# BaliseEmetteur.net
KiCad netlist of a schematic drawn in EAGLE
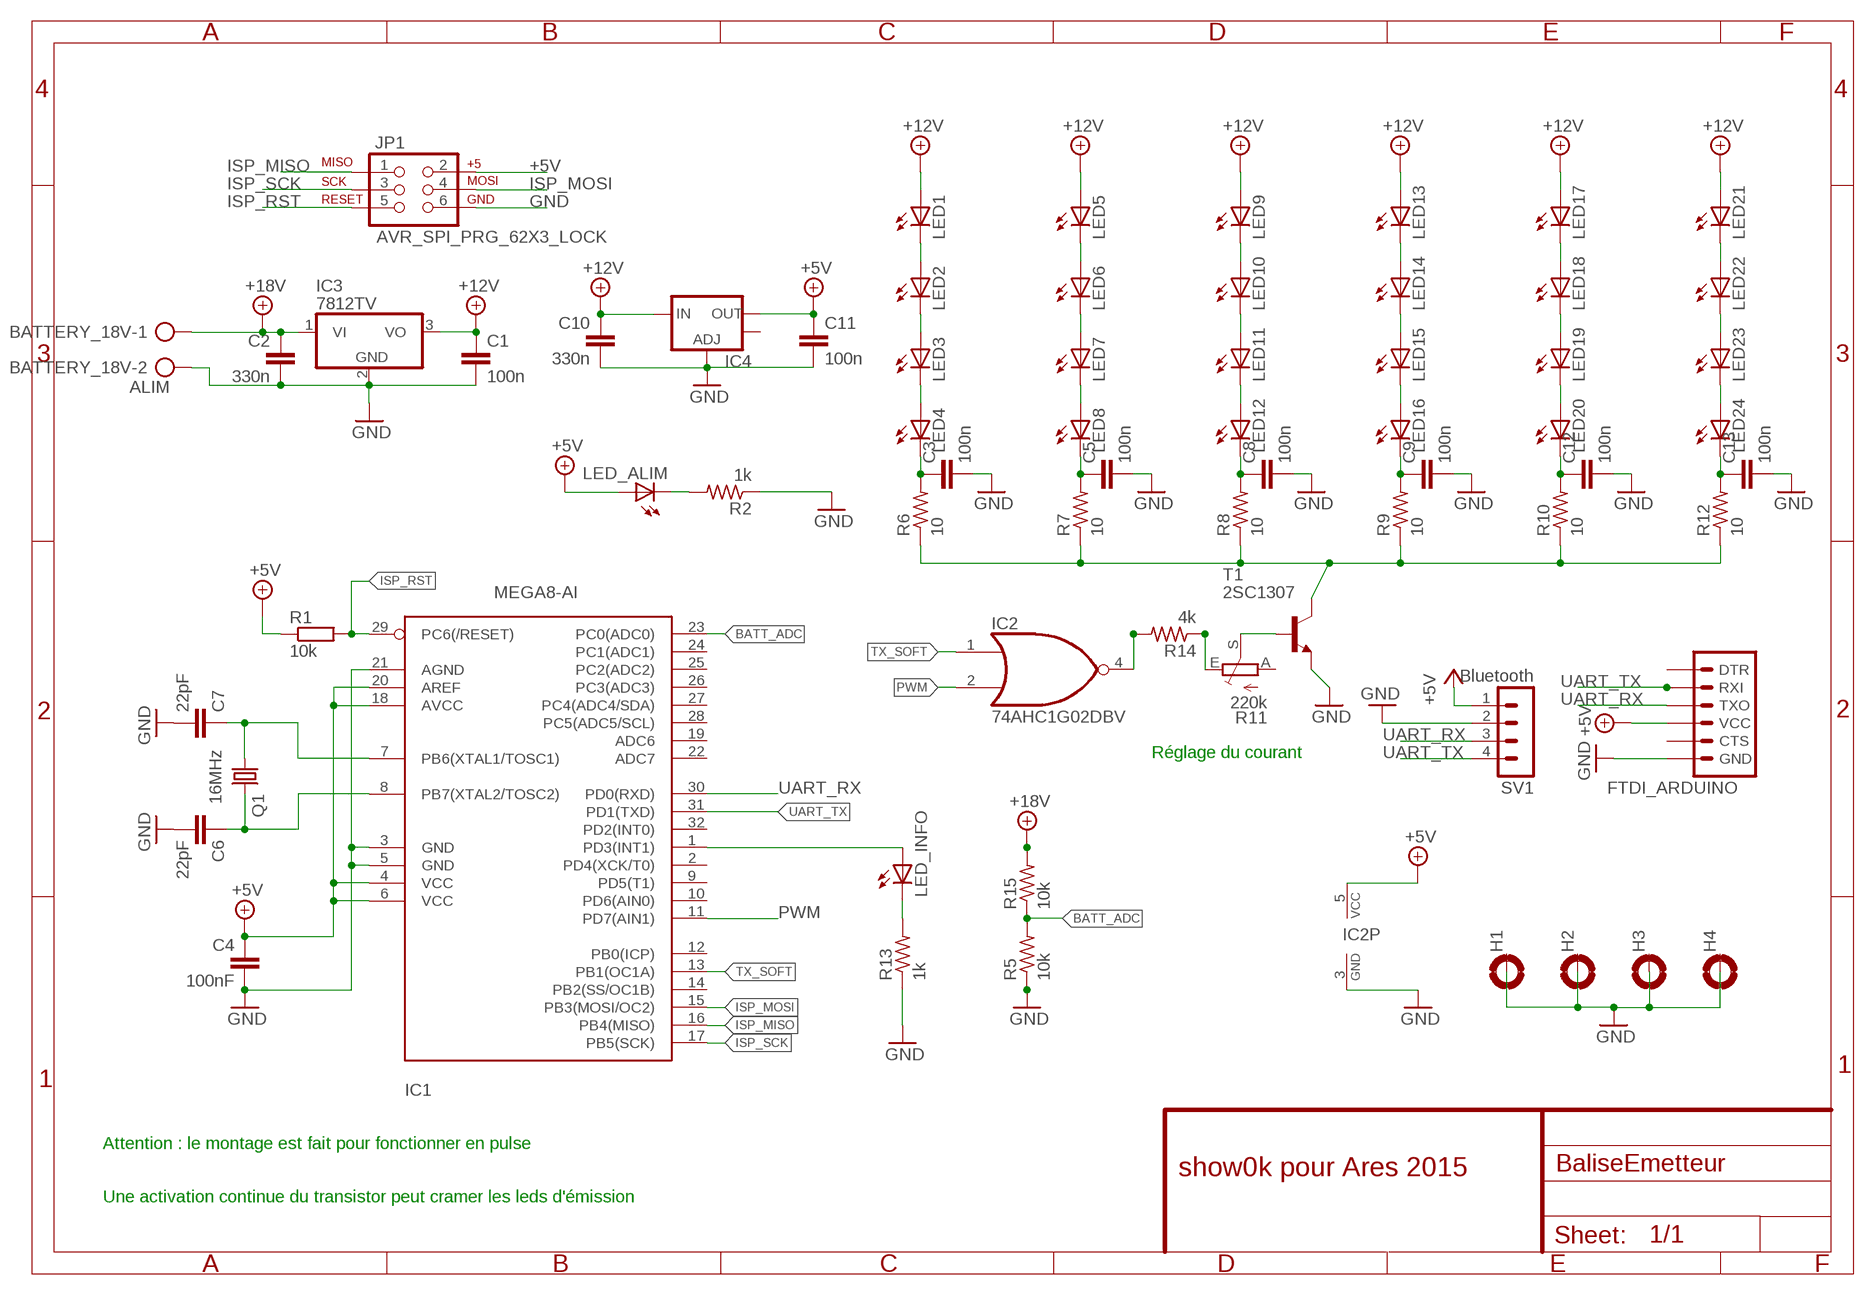
[diagram p0: schematic, sheet 1]

(export (version "E")
  (design (tool "Eeschema 10.0.6"))
  (components
    (comp (ref "BATTERY_18V")
      (value "ALIM")
      (footprint "eagle-import:AK500_2")
      (libsource (lib "eagle-import") (part "AK500/2"))
    )
    (comp (ref "C1")
      (value "100n")
      (footprint "eagle-import:C0805")
      (libsource (lib "eagle-import") (part "C-EUC0805"))
    )
    (comp (ref "C2")
      (value "330n")
      (footprint "eagle-import:C0805")
      (libsource (lib "eagle-import") (part "C-EUC0805"))
    )
    (comp (ref "C3")
      (value "100n")
      (footprint "eagle-import:C0805")
      (libsource (lib "eagle-import") (part "C-EUC0805"))
    )
    (comp (ref "C4")
      (value "100nF")
      (footprint "eagle-import:C0805")
      (libsource (lib "eagle-import") (part "C-EUC0805"))
    )
    (comp (ref "C5")
      (value "100n")
      (footprint "eagle-import:C0805")
      (libsource (lib "eagle-import") (part "C-EUC0805"))
    )
    (comp (ref "C6")
      (value "22pF")
      (footprint "eagle-import:C0805")
      (libsource (lib "eagle-import") (part "C-EUC0805"))
    )
    (comp (ref "C7")
      (value "22pF")
      (footprint "eagle-import:C0805")
      (libsource (lib "eagle-import") (part "C-EUC0805"))
    )
    (comp (ref "C8")
      (value "100n")
      (footprint "eagle-import:C0805")
      (libsource (lib "eagle-import") (part "C-EUC0805"))
    )
    (comp (ref "C9")
      (value "100n")
      (footprint "eagle-import:C0805")
      (libsource (lib "eagle-import") (part "C-EUC0805"))
    )
    (comp (ref "C10")
      (value "330n")
      (footprint "eagle-import:C0805")
      (libsource (lib "eagle-import") (part "C-EUC0805"))
    )
    (comp (ref "C11")
      (value "100n")
      (footprint "eagle-import:C0805")
      (libsource (lib "eagle-import") (part "C-EUC0805"))
    )
    (comp (ref "C12")
      (value "100n")
      (footprint "eagle-import:C0805")
      (libsource (lib "eagle-import") (part "C-EUC0805"))
    )
    (comp (ref "C13")
      (value "100n")
      (footprint "eagle-import:C0805")
      (libsource (lib "eagle-import") (part "C-EUC0805"))
    )
    (comp (ref "FTDI_ARDUINO")
      (value "ARDUINO_SERIAL_PROGRAMPTH")
      (footprint "eagle-import:1X06")
      (libsource (lib "eagle-import") (part "ARDUINO_SERIAL_PROGRAMPTH"))
    )
    (comp (ref "H1")
      (value "MOUNT-PAD-ROUND3.2")
      (footprint "eagle-import:3,2-PAD")
      (libsource (lib "eagle-import") (part "MOUNT-PAD-ROUND3.2"))
    )
    (comp (ref "H2")
      (value "MOUNT-PAD-ROUND3.2")
      (footprint "eagle-import:3,2-PAD")
      (libsource (lib "eagle-import") (part "MOUNT-PAD-ROUND3.2"))
    )
    (comp (ref "H3")
      (value "MOUNT-PAD-ROUND3.2")
      (footprint "eagle-import:3,2-PAD")
      (libsource (lib "eagle-import") (part "MOUNT-PAD-ROUND3.2"))
    )
    (comp (ref "H4")
      (value "MOUNT-PAD-ROUND3.2")
      (footprint "eagle-import:3,2-PAD")
      (libsource (lib "eagle-import") (part "MOUNT-PAD-ROUND3.2"))
    )
    (comp (ref "IC1")
      (value "MEGA8-AI")
      (footprint "eagle-import:TQFP32-08")
      (libsource (lib "eagle-import") (part "MEGA8-AI"))
    )
    (comp (ref "IC2")
      (value "74AHC1G02DBV")
      (footprint "eagle-import:SOT23-5")
      (libsource (lib "eagle-import") (part "741G02DBVAHC"))
    )
    (comp (ref "IC3")
      (value "7812TV")
      (footprint "eagle-import:TO220V")
      (libsource (lib "eagle-import") (part "78TV12"))
    )
    (comp (ref "IC4")
      (value "V_REG_LM1117SOT223")
      (footprint "eagle-import:SOT223")
      (libsource (lib "eagle-import") (part "V_REG_LM1117SOT223"))
    )
    (comp (ref "JP1")
      (value "AVR_SPI_PRG_62X3_LOCK")
      (footprint "eagle-import:2X3_LOCK")
      (libsource (lib "eagle-import") (part "AVR_SPI_PRG_62X3_LOCK"))
    )
    (comp (ref "LED1")
      (value "LEDB155")
      (footprint "eagle-import:Q62902-B155")
      (libsource (lib "eagle-import") (part "led_LEDB155"))
    )
    (comp (ref "LED2")
      (value "LEDB155")
      (footprint "eagle-import:Q62902-B155")
      (libsource (lib "eagle-import") (part "led_LEDB155"))
    )
    (comp (ref "LED3")
      (value "LEDB155")
      (footprint "eagle-import:Q62902-B155")
      (libsource (lib "eagle-import") (part "led_LEDB155"))
    )
    (comp (ref "LED4")
      (value "LEDB155")
      (footprint "eagle-import:Q62902-B155")
      (libsource (lib "eagle-import") (part "led_LEDB155"))
    )
    (comp (ref "LED5")
      (value "LEDB155")
      (footprint "eagle-import:Q62902-B155")
      (libsource (lib "eagle-import") (part "led_LEDB155"))
    )
    (comp (ref "LED6")
      (value "LEDB155")
      (footprint "eagle-import:Q62902-B155")
      (libsource (lib "eagle-import") (part "led_LEDB155"))
    )
    (comp (ref "LED7")
      (value "LEDB155")
      (footprint "eagle-import:Q62902-B155")
      (libsource (lib "eagle-import") (part "led_LEDB155"))
    )
    (comp (ref "LED8")
      (value "LEDB155")
      (footprint "eagle-import:Q62902-B155")
      (libsource (lib "eagle-import") (part "led_LEDB155"))
    )
    (comp (ref "LED9")
      (value "LEDB155")
      (footprint "eagle-import:Q62902-B155")
      (libsource (lib "eagle-import") (part "led_LEDB155"))
    )
    (comp (ref "LED10")
      (value "LEDB155")
      (footprint "eagle-import:Q62902-B155")
      (libsource (lib "eagle-import") (part "led_LEDB155"))
    )
    (comp (ref "LED11")
      (value "LEDB155")
      (footprint "eagle-import:Q62902-B155")
      (libsource (lib "eagle-import") (part "led_LEDB155"))
    )
    (comp (ref "LED12")
      (value "LEDB155")
      (footprint "eagle-import:Q62902-B155")
      (libsource (lib "eagle-import") (part "led_LEDB155"))
    )
    (comp (ref "LED13")
      (value "LEDB155")
      (footprint "eagle-import:Q62902-B155")
      (libsource (lib "eagle-import") (part "led_LEDB155"))
    )
    (comp (ref "LED14")
      (value "LEDB155")
      (footprint "eagle-import:Q62902-B155")
      (libsource (lib "eagle-import") (part "led_LEDB155"))
    )
    (comp (ref "LED15")
      (value "LEDB155")
      (footprint "eagle-import:Q62902-B155")
      (libsource (lib "eagle-import") (part "led_LEDB155"))
    )
    (comp (ref "LED16")
      (value "LEDB155")
      (footprint "eagle-import:Q62902-B155")
      (libsource (lib "eagle-import") (part "led_LEDB155"))
    )
    (comp (ref "LED17")
      (value "LEDB155")
      (footprint "eagle-import:Q62902-B155")
      (libsource (lib "eagle-import") (part "led_LEDB155"))
    )
    (comp (ref "LED18")
      (value "LEDB155")
      (footprint "eagle-import:Q62902-B155")
      (libsource (lib "eagle-import") (part "led_LEDB155"))
    )
    (comp (ref "LED19")
      (value "LEDB155")
      (footprint "eagle-import:Q62902-B155")
      (libsource (lib "eagle-import") (part "led_LEDB155"))
    )
    (comp (ref "LED20")
      (value "LEDB155")
      (footprint "eagle-import:Q62902-B155")
      (libsource (lib "eagle-import") (part "led_LEDB155"))
    )
    (comp (ref "LED21")
      (value "LEDB155")
      (footprint "eagle-import:Q62902-B155")
      (libsource (lib "eagle-import") (part "led_LEDB155"))
    )
    (comp (ref "LED22")
      (value "LEDB155")
      (footprint "eagle-import:Q62902-B155")
      (libsource (lib "eagle-import") (part "led_LEDB155"))
    )
    (comp (ref "LED23")
      (value "LEDB155")
      (footprint "eagle-import:Q62902-B155")
      (libsource (lib "eagle-import") (part "led_LEDB155"))
    )
    (comp (ref "LED24")
      (value "LEDB155")
      (footprint "eagle-import:Q62902-B155")
      (libsource (lib "eagle-import") (part "led_LEDB155"))
    )
    (comp (ref "LED_ALIM")
      (value "LEDCHIPLED_0805")
      (footprint "eagle-import:CHIPLED_0805")
      (libsource (lib "eagle-import") (part "LEDCHIPLED_0805"))
    )
    (comp (ref "LED_INFO")
      (value "LEDCHIPLED_0805")
      (footprint "eagle-import:CHIPLED_0805")
      (libsource (lib "eagle-import") (part "LEDCHIPLED_0805"))
    )
    (comp (ref "Q1")
      (value "16MHz")
      (footprint "eagle-import:HC49_S")
      (libsource (lib "eagle-import") (part "CRYSTALHC49S"))
    )
    (comp (ref "R1")
      (value "10k")
      (footprint "eagle-import:0207_2V")
      (libsource (lib "eagle-import") (part "R-EU_0207/2V"))
    )
    (comp (ref "R2")
      (value "1k")
      (footprint "eagle-import:M0805")
      (libsource (lib "eagle-import") (part "R-US_M0805"))
    )
    (comp (ref "R5")
      (value "10k")
      (footprint "eagle-import:M0805")
      (libsource (lib "eagle-import") (part "R-US_M0805"))
    )
    (comp (ref "R6")
      (value "10")
      (footprint "eagle-import:M0805")
      (libsource (lib "eagle-import") (part "R-US_M0805"))
    )
    (comp (ref "R7")
      (value "10")
      (footprint "eagle-import:M0805")
      (libsource (lib "eagle-import") (part "R-US_M0805"))
    )
    (comp (ref "R8")
      (value "10")
      (footprint "eagle-import:M0805")
      (libsource (lib "eagle-import") (part "R-US_M0805"))
    )
    (comp (ref "R9")
      (value "10")
      (footprint "eagle-import:M0805")
      (libsource (lib "eagle-import") (part "R-US_M0805"))
    )
    (comp (ref "R10")
      (value "10")
      (footprint "eagle-import:M0805")
      (libsource (lib "eagle-import") (part "R-US_M0805"))
    )
    (comp (ref "R11")
      (value "220k")
      (footprint "eagle-import:CA9V")
      (libsource (lib "eagle-import") (part "TRIM_EU-CA9V"))
    )
    (comp (ref "R12")
      (value "10")
      (footprint "eagle-import:M0805")
      (libsource (lib "eagle-import") (part "R-US_M0805"))
    )
    (comp (ref "R13")
      (value "1k")
      (footprint "eagle-import:M0805")
      (libsource (lib "eagle-import") (part "R-US_M0805"))
    )
    (comp (ref "R14")
      (value "4k")
      (footprint "eagle-import:M0805")
      (libsource (lib "eagle-import") (part "R-US_M0805"))
    )
    (comp (ref "R15")
      (value "10k")
      (footprint "eagle-import:M0805")
      (libsource (lib "eagle-import") (part "R-US_M0805"))
    )
    (comp (ref "SV1")
      (value "Bluetooth")
      (footprint "eagle-import:MA04-1")
      (libsource (lib "eagle-import") (part "MA04-1"))
    )
    (comp (ref "T1")
      (value "2SC1307")
      (footprint "eagle-import:TO220AV")
      (libsource (lib "eagle-import") (part "2SC1307"))
    )
  )
  (nets
    (net (code "1") (name "+5V") (class "Default")
      (node (ref "C11") (pin "1") (pinfunction "1_1") (pintype "passive"))
      (node (ref "C4") (pin "1") (pinfunction "1_1") (pintype "passive"))
      (node (ref "FTDI_ARDUINO") (pin "4") (pinfunction "VCC_4") (pintype "passive"))
      (node (ref "IC1") (pin "18") (pinfunction "AVCC_18") (pintype "power_in"))
      (node (ref "IC1") (pin "20") (pinfunction "AREF_20") (pintype "passive"))
      (node (ref "IC1") (pin "4") (pinfunction "VCC_4") (pintype "power_in"))
      (node (ref "IC1") (pin "6") (pinfunction "VCC_6") (pintype "power_in"))
      (node (ref "IC2") (pin "5") (pinfunction "VCC_5") (pintype "power_in"))
      (node (ref "IC4") (pin "2") (pinfunction "OUT_2") (pintype "output"))
      (node (ref "JP1") (pin "2") (pinfunction "2_2") (pintype "passive"))
      (node (ref "LED_ALIM") (pin "A") (pinfunction "A_A") (pintype "passive"))
      (node (ref "R1") (pin "1") (pinfunction "1_1") (pintype "passive"))
      (node (ref "SV1") (pin "1") (pinfunction "1_1") (pintype "passive"))
    )
    (net (code "2") (name "+12V") (class "Default")
      (node (ref "C1") (pin "1") (pinfunction "1_1") (pintype "passive"))
      (node (ref "C10") (pin "1") (pinfunction "1_1") (pintype "passive"))
      (node (ref "IC3") (pin "3") (pinfunction "VO_3") (pintype "passive"))
      (node (ref "IC4") (pin "3") (pinfunction "IN_3") (pintype "input"))
      (node (ref "LED1") (pin "A") (pinfunction "A_A") (pintype "passive"))
      (node (ref "LED13") (pin "A") (pinfunction "A_A") (pintype "passive"))
      (node (ref "LED17") (pin "A") (pinfunction "A_A") (pintype "passive"))
      (node (ref "LED21") (pin "A") (pinfunction "A_A") (pintype "passive"))
      (node (ref "LED5") (pin "A") (pinfunction "A_A") (pintype "passive"))
      (node (ref "LED9") (pin "A") (pinfunction "A_A") (pintype "passive"))
    )
    (net (code "3") (name "+18V") (class "Default")
      (node (ref "BATTERY_18V") (pin "1") (pinfunction "KL_1") (pintype "passive"))
      (node (ref "C2") (pin "1") (pinfunction "1_1") (pintype "passive"))
      (node (ref "IC3") (pin "1") (pinfunction "VI_1") (pintype "input"))
      (node (ref "R15") (pin "2") (pinfunction "2_2") (pintype "passive"))
    )
    (net (code "4") (name "/UART_RX") (class "Default")
      (node (ref "FTDI_ARDUINO") (pin "3") (pinfunction "TXO_3") (pintype "passive"))
      (node (ref "IC1") (pin "30") (pinfunction "PD0(RXD)_30") (pintype "bidirectional"))
      (node (ref "SV1") (pin "3") (pinfunction "3_3") (pintype "passive"))
    )
    (net (code "5") (name "BATT_ADC") (class "Default")
      (node (ref "IC1") (pin "23") (pinfunction "PC0(ADC0)_23") (pintype "bidirectional"))
      (node (ref "R15") (pin "1") (pinfunction "1_1") (pintype "passive"))
      (node (ref "R5") (pin "2") (pinfunction "2_2") (pintype "passive"))
    )
    (net (code "6") (name "GND") (class "Default")
      (node (ref "BATTERY_18V") (pin "2") (pinfunction "KL_2") (pintype "passive"))
      (node (ref "C1") (pin "2") (pinfunction "2_2") (pintype "passive"))
      (node (ref "C10") (pin "2") (pinfunction "2_2") (pintype "passive"))
      (node (ref "C11") (pin "2") (pinfunction "2_2") (pintype "passive"))
      (node (ref "C12") (pin "2") (pinfunction "2_2") (pintype "passive"))
      (node (ref "C13") (pin "2") (pinfunction "2_2") (pintype "passive"))
      (node (ref "C2") (pin "2") (pinfunction "2_2") (pintype "passive"))
      (node (ref "C3") (pin "2") (pinfunction "2_2") (pintype "passive"))
      (node (ref "C4") (pin "2") (pinfunction "2_2") (pintype "passive"))
      (node (ref "C5") (pin "2") (pinfunction "2_2") (pintype "passive"))
      (node (ref "C6") (pin "2") (pinfunction "2_2") (pintype "passive"))
      (node (ref "C7") (pin "2") (pinfunction "2_2") (pintype "passive"))
      (node (ref "C8") (pin "2") (pinfunction "2_2") (pintype "passive"))
      (node (ref "C9") (pin "2") (pinfunction "2_2") (pintype "passive"))
      (node (ref "FTDI_ARDUINO") (pin "6") (pinfunction "GND_6") (pintype "passive"))
      (node (ref "H1") (pin "B3,2") (pinfunction "MOUNT_B3,2") (pintype "passive"))
      (node (ref "H2") (pin "B3,2") (pinfunction "MOUNT_B3,2") (pintype "passive"))
      (node (ref "H3") (pin "B3,2") (pinfunction "MOUNT_B3,2") (pintype "passive"))
      (node (ref "H4") (pin "B3,2") (pinfunction "MOUNT_B3,2") (pintype "passive"))
      (node (ref "IC1") (pin "21") (pinfunction "AGND_21") (pintype "power_in"))
      (node (ref "IC1") (pin "3") (pinfunction "GND_3") (pintype "power_in"))
      (node (ref "IC1") (pin "5") (pinfunction "GND_5") (pintype "power_in"))
      (node (ref "IC2") (pin "3") (pinfunction "GND_3") (pintype "power_in"))
      (node (ref "IC3") (pin "2") (pinfunction "GND_2") (pintype "passive"))
      (node (ref "IC4") (pin "1") (pinfunction "ADJ_1") (pintype "input"))
      (node (ref "JP1") (pin "6") (pinfunction "6_6") (pintype "passive"))
      (node (ref "R13") (pin "1") (pinfunction "1_1") (pintype "passive"))
      (node (ref "R2") (pin "1") (pinfunction "1_1") (pintype "passive"))
      (node (ref "R5") (pin "1") (pinfunction "1_1") (pintype "passive"))
      (node (ref "SV1") (pin "2") (pinfunction "2_2") (pintype "passive"))
      (node (ref "T1") (pin "3") (pinfunction "E_3") (pintype "passive"))
    )
    (net (code "7") (name "ISP_MISO") (class "Default")
      (node (ref "IC1") (pin "16") (pinfunction "PB4(MISO)_16") (pintype "bidirectional"))
      (node (ref "JP1") (pin "1") (pinfunction "1_1") (pintype "passive"))
    )
    (net (code "8") (name "ISP_MOSI") (class "Default")
      (node (ref "IC1") (pin "15") (pinfunction "PB3(MOSI/OC2)_15") (pintype "bidirectional"))
      (node (ref "JP1") (pin "4") (pinfunction "4_4") (pintype "passive"))
    )
    (net (code "9") (name "ISP_RST") (class "Default")
      (node (ref "IC1") (pin "29") (pinfunction "PC6(/RESET)_29") (pintype "bidirectional"))
      (node (ref "JP1") (pin "5") (pinfunction "5_5") (pintype "passive"))
      (node (ref "R1") (pin "2") (pinfunction "2_2") (pintype "passive"))
    )
    (net (code "10") (name "ISP_SCK") (class "Default")
      (node (ref "IC1") (pin "17") (pinfunction "PB5(SCK)_17") (pintype "bidirectional"))
      (node (ref "JP1") (pin "3") (pinfunction "3_3") (pintype "passive"))
    )
    (net (code "11") (name "Net-(IC1-PB6(XTAL1{slash}TOSC1))") (class "Default")
      (node (ref "C7") (pin "1") (pinfunction "1_1") (pintype "passive"))
      (node (ref "IC1") (pin "7") (pinfunction "PB6(XTAL1/TOSC1)_7") (pintype "bidirectional"))
      (node (ref "Q1") (pin "1") (pinfunction "1_1") (pintype "passive"))
    )
    (net (code "12") (name "Net-(IC1-PB7(XTAL2{slash}TOSC2))") (class "Default")
      (node (ref "C6") (pin "1") (pinfunction "1_1") (pintype "passive"))
      (node (ref "IC1") (pin "8") (pinfunction "PB7(XTAL2/TOSC2)_8") (pintype "bidirectional"))
      (node (ref "Q1") (pin "2") (pinfunction "2_2") (pintype "passive"))
    )
    (net (code "13") (name "Net-(IC1-PD3(INT1))") (class "Default")
      (node (ref "IC1") (pin "1") (pinfunction "PD3(INT1)_1") (pintype "bidirectional"))
      (node (ref "LED_INFO") (pin "A") (pinfunction "A_A") (pintype "passive"))
    )
    (net (code "14") (name "Net-(IC2A-O)") (class "Default")
      (node (ref "IC2") (pin "4") (pinfunction "O_4") (pintype "output"))
      (node (ref "R14") (pin "2") (pinfunction "2_2") (pintype "passive"))
    )
    (net (code "15") (name "Net-(LED1-C)") (class "Default")
      (node (ref "LED1") (pin "K") (pinfunction "C_K") (pintype "passive"))
      (node (ref "LED2") (pin "A") (pinfunction "A_A") (pintype "passive"))
    )
    (net (code "16") (name "Net-(LED2-C)") (class "Default")
      (node (ref "LED2") (pin "K") (pinfunction "C_K") (pintype "passive"))
      (node (ref "LED3") (pin "A") (pinfunction "A_A") (pintype "passive"))
    )
    (net (code "17") (name "Net-(LED3-C)") (class "Default")
      (node (ref "LED3") (pin "K") (pinfunction "C_K") (pintype "passive"))
      (node (ref "LED4") (pin "A") (pinfunction "A_A") (pintype "passive"))
    )
    (net (code "18") (name "Net-(LED4-C)") (class "Default")
      (node (ref "C3") (pin "1") (pinfunction "1_1") (pintype "passive"))
      (node (ref "LED4") (pin "K") (pinfunction "C_K") (pintype "passive"))
      (node (ref "R6") (pin "2") (pinfunction "2_2") (pintype "passive"))
    )
    (net (code "19") (name "Net-(LED5-C)") (class "Default")
      (node (ref "LED5") (pin "K") (pinfunction "C_K") (pintype "passive"))
      (node (ref "LED6") (pin "A") (pinfunction "A_A") (pintype "passive"))
    )
    (net (code "20") (name "Net-(LED6-C)") (class "Default")
      (node (ref "LED6") (pin "K") (pinfunction "C_K") (pintype "passive"))
      (node (ref "LED7") (pin "A") (pinfunction "A_A") (pintype "passive"))
    )
    (net (code "21") (name "Net-(LED7-C)") (class "Default")
      (node (ref "LED7") (pin "K") (pinfunction "C_K") (pintype "passive"))
      (node (ref "LED8") (pin "A") (pinfunction "A_A") (pintype "passive"))
    )
    (net (code "22") (name "Net-(LED8-C)") (class "Default")
      (node (ref "C5") (pin "1") (pinfunction "1_1") (pintype "passive"))
      (node (ref "LED8") (pin "K") (pinfunction "C_K") (pintype "passive"))
      (node (ref "R7") (pin "2") (pinfunction "2_2") (pintype "passive"))
    )
    (net (code "23") (name "Net-(LED9-C)") (class "Default")
      (node (ref "LED10") (pin "A") (pinfunction "A_A") (pintype "passive"))
      (node (ref "LED9") (pin "K") (pinfunction "C_K") (pintype "passive"))
    )
    (net (code "24") (name "Net-(LED10-C)") (class "Default")
      (node (ref "LED10") (pin "K") (pinfunction "C_K") (pintype "passive"))
      (node (ref "LED11") (pin "A") (pinfunction "A_A") (pintype "passive"))
    )
    (net (code "25") (name "Net-(LED11-C)") (class "Default")
      (node (ref "LED11") (pin "K") (pinfunction "C_K") (pintype "passive"))
      (node (ref "LED12") (pin "A") (pinfunction "A_A") (pintype "passive"))
    )
    (net (code "26") (name "Net-(LED12-C)") (class "Default")
      (node (ref "C8") (pin "1") (pinfunction "1_1") (pintype "passive"))
      (node (ref "LED12") (pin "K") (pinfunction "C_K") (pintype "passive"))
      (node (ref "R8") (pin "2") (pinfunction "2_2") (pintype "passive"))
    )
    (net (code "27") (name "Net-(LED13-C)") (class "Default")
      (node (ref "LED13") (pin "K") (pinfunction "C_K") (pintype "passive"))
      (node (ref "LED14") (pin "A") (pinfunction "A_A") (pintype "passive"))
    )
    (net (code "28") (name "Net-(LED14-C)") (class "Default")
      (node (ref "LED14") (pin "K") (pinfunction "C_K") (pintype "passive"))
      (node (ref "LED15") (pin "A") (pinfunction "A_A") (pintype "passive"))
    )
    (net (code "29") (name "Net-(LED15-C)") (class "Default")
      (node (ref "LED15") (pin "K") (pinfunction "C_K") (pintype "passive"))
      (node (ref "LED16") (pin "A") (pinfunction "A_A") (pintype "passive"))
    )
    (net (code "30") (name "Net-(LED16-C)") (class "Default")
      (node (ref "C9") (pin "1") (pinfunction "1_1") (pintype "passive"))
      (node (ref "LED16") (pin "K") (pinfunction "C_K") (pintype "passive"))
      (node (ref "R9") (pin "2") (pinfunction "2_2") (pintype "passive"))
    )
    (net (code "31") (name "Net-(LED17-C)") (class "Default")
      (node (ref "LED17") (pin "K") (pinfunction "C_K") (pintype "passive"))
      (node (ref "LED18") (pin "A") (pinfunction "A_A") (pintype "passive"))
    )
    (net (code "32") (name "Net-(LED18-C)") (class "Default")
      (node (ref "LED18") (pin "K") (pinfunction "C_K") (pintype "passive"))
      (node (ref "LED19") (pin "A") (pinfunction "A_A") (pintype "passive"))
    )
    (net (code "33") (name "Net-(LED19-C)") (class "Default")
      (node (ref "LED19") (pin "K") (pinfunction "C_K") (pintype "passive"))
      (node (ref "LED20") (pin "A") (pinfunction "A_A") (pintype "passive"))
    )
    (net (code "34") (name "Net-(LED20-C)") (class "Default")
      (node (ref "C12") (pin "1") (pinfunction "1_1") (pintype "passive"))
      (node (ref "LED20") (pin "K") (pinfunction "C_K") (pintype "passive"))
      (node (ref "R10") (pin "2") (pinfunction "2_2") (pintype "passive"))
    )
    (net (code "35") (name "Net-(LED21-C)") (class "Default")
      (node (ref "LED21") (pin "K") (pinfunction "C_K") (pintype "passive"))
      (node (ref "LED22") (pin "A") (pinfunction "A_A") (pintype "passive"))
    )
    (net (code "36") (name "Net-(LED22-C)") (class "Default")
      (node (ref "LED22") (pin "K") (pinfunction "C_K") (pintype "passive"))
      (node (ref "LED23") (pin "A") (pinfunction "A_A") (pintype "passive"))
    )
    (net (code "37") (name "Net-(LED23-C)") (class "Default")
      (node (ref "LED23") (pin "K") (pinfunction "C_K") (pintype "passive"))
      (node (ref "LED24") (pin "A") (pinfunction "A_A") (pintype "passive"))
    )
    (net (code "38") (name "Net-(LED24-C)") (class "Default")
      (node (ref "C13") (pin "1") (pinfunction "1_1") (pintype "passive"))
      (node (ref "LED24") (pin "K") (pinfunction "C_K") (pintype "passive"))
      (node (ref "R12") (pin "2") (pinfunction "2_2") (pintype "passive"))
    )
    (net (code "39") (name "Net-(LED_ALIM-PadC)") (class "Default")
      (node (ref "LED_ALIM") (pin "C") (pinfunction "C_C") (pintype "passive"))
      (node (ref "R2") (pin "2") (pinfunction "2_2") (pintype "passive"))
    )
    (net (code "40") (name "Net-(LED_INFO-PadC)") (class "Default")
      (node (ref "LED_INFO") (pin "C") (pinfunction "C_C") (pintype "passive"))
      (node (ref "R13") (pin "2") (pinfunction "2_2") (pintype "passive"))
    )
    (net (code "41") (name "Net-(R11-PadE)") (class "Default")
      (node (ref "R11") (pin "E") (pinfunction "E_E") (pintype "passive"))
      (node (ref "R14") (pin "1") (pinfunction "1_1") (pintype "passive"))
    )
    (net (code "42") (name "Net-(T1-B)") (class "Default")
      (node (ref "R11") (pin "S") (pinfunction "S_S") (pintype "passive"))
      (node (ref "T1") (pin "1") (pinfunction "B_1") (pintype "passive"))
    )
    (net (code "43") (name "Net-(T1-C)") (class "Default")
      (node (ref "R10") (pin "1") (pinfunction "1_1") (pintype "passive"))
      (node (ref "R12") (pin "1") (pinfunction "1_1") (pintype "passive"))
      (node (ref "R6") (pin "1") (pinfunction "1_1") (pintype "passive"))
      (node (ref "R7") (pin "1") (pinfunction "1_1") (pintype "passive"))
      (node (ref "R8") (pin "1") (pinfunction "1_1") (pintype "passive"))
      (node (ref "R9") (pin "1") (pinfunction "1_1") (pintype "passive"))
      (node (ref "T1") (pin "2") (pinfunction "C_2") (pintype "passive"))
    )
    (net (code "44") (name "PWM") (class "Default")
      (node (ref "IC1") (pin "11") (pinfunction "PD7(AIN1)_11") (pintype "bidirectional"))
      (node (ref "IC2") (pin "2") (pinfunction "I1_2") (pintype "input"))
    )
    (net (code "45") (name "TX_SOFT") (class "Default")
      (node (ref "IC1") (pin "13") (pinfunction "PB1(OC1A)_13") (pintype "bidirectional"))
      (node (ref "IC2") (pin "1") (pinfunction "I0_1") (pintype "input"))
    )
    (net (code "46") (name "UART_TX") (class "Default")
      (node (ref "FTDI_ARDUINO") (pin "2") (pinfunction "RXI_2") (pintype "passive"))
      (node (ref "IC1") (pin "31") (pinfunction "PD1(TXD)_31") (pintype "bidirectional"))
      (node (ref "SV1") (pin "4") (pinfunction "4_4") (pintype "passive"))
    )
    (net (code "47") (name "unconnected-(FTDI_ARDUINO-CTS-Pad5)") (class "Default")
      (node (ref "FTDI_ARDUINO") (pin "5") (pinfunction "CTS_5") (pintype "passive"))
    )
    (net (code "48") (name "unconnected-(FTDI_ARDUINO-DTR-Pad1)") (class "Default")
      (node (ref "FTDI_ARDUINO") (pin "1") (pinfunction "DTR_1") (pintype "passive"))
    )
    (net (code "49") (name "unconnected-(IC1-ADC6-Pad19)") (class "Default")
      (node (ref "IC1") (pin "19") (pinfunction "ADC6_19") (pintype "bidirectional"))
    )
    (net (code "50") (name "unconnected-(IC1-ADC7-Pad22)") (class "Default")
      (node (ref "IC1") (pin "22") (pinfunction "ADC7_22") (pintype "bidirectional"))
    )
    (net (code "51") (name "unconnected-(IC1-PB0(ICP)-Pad12)") (class "Default")
      (node (ref "IC1") (pin "12") (pinfunction "PB0(ICP)_12") (pintype "bidirectional"))
    )
    (net (code "52") (name "unconnected-(IC1-PB2(SS{slash}OC1B)-Pad14)") (class "Default")
      (node (ref "IC1") (pin "14") (pinfunction "PB2(SS/OC1B)_14") (pintype "bidirectional"))
    )
    (net (code "53") (name "unconnected-(IC1-PC1(ADC1)-Pad24)") (class "Default")
      (node (ref "IC1") (pin "24") (pinfunction "PC1(ADC1)_24") (pintype "bidirectional"))
    )
    (net (code "54") (name "unconnected-(IC1-PC2(ADC2)-Pad25)") (class "Default")
      (node (ref "IC1") (pin "25") (pinfunction "PC2(ADC2)_25") (pintype "bidirectional"))
    )
    (net (code "55") (name "unconnected-(IC1-PC3(ADC3)-Pad26)") (class "Default")
      (node (ref "IC1") (pin "26") (pinfunction "PC3(ADC3)_26") (pintype "bidirectional"))
    )
    (net (code "56") (name "unconnected-(IC1-PC4(ADC4{slash}SDA)-Pad27)") (class "Default")
      (node (ref "IC1") (pin "27") (pinfunction "PC4(ADC4/SDA)_27") (pintype "bidirectional"))
    )
    (net (code "57") (name "unconnected-(IC1-PC5(ADC5{slash}SCL)-Pad28)") (class "Default")
      (node (ref "IC1") (pin "28") (pinfunction "PC5(ADC5/SCL)_28") (pintype "bidirectional"))
    )
    (net (code "58") (name "unconnected-(IC1-PD2(INT0)-Pad32)") (class "Default")
      (node (ref "IC1") (pin "32") (pinfunction "PD2(INT0)_32") (pintype "bidirectional"))
    )
    (net (code "59") (name "unconnected-(IC1-PD4(XCK{slash}T0)-Pad2)") (class "Default")
      (node (ref "IC1") (pin "2") (pinfunction "PD4(XCK/T0)_2") (pintype "bidirectional"))
    )
    (net (code "60") (name "unconnected-(IC1-PD5(T1)-Pad9)") (class "Default")
      (node (ref "IC1") (pin "9") (pinfunction "PD5(T1)_9") (pintype "bidirectional"))
    )
    (net (code "61") (name "unconnected-(IC1-PD6(AIN0)-Pad10)") (class "Default")
      (node (ref "IC1") (pin "10") (pinfunction "PD6(AIN0)_10") (pintype "bidirectional"))
    )
    (net (code "62") (name "unconnected-(IC4-OUT-Pad4)") (class "Default")
      (node (ref "IC4") (pin "4") (pinfunction "OUT_4") (pintype "output"))
    )
    (net (code "63") (name "unconnected-(R11-PadA)") (class "Default")
      (node (ref "R11") (pin "A") (pinfunction "A_A") (pintype "passive"))
    )
  )
)
